# PIC_Schematic.net
KiCad netlist of a schematic drawn in Altium Designer
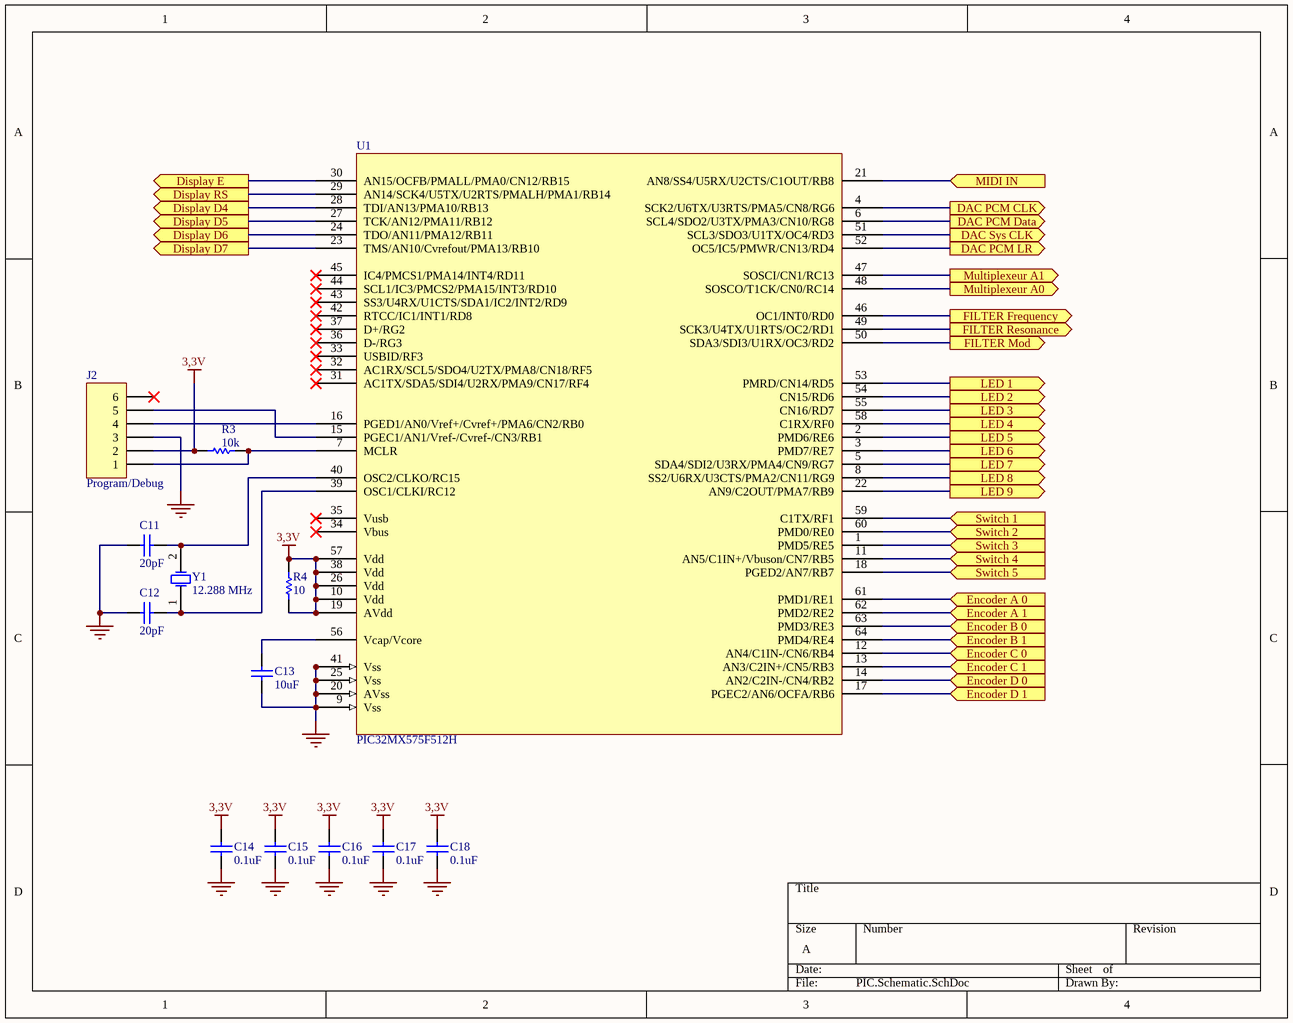
[diagram p0: PIC.Schematic.SchDoc]

(export (version "E")
  (design (tool "Eeschema 10.0.6"))
  (components
    (comp (ref "C11")
      (value "20pF")
      (footprint "CAPC1608N")
      (description "Capacitor (Semiconductor SIM Model)")
      (fields (field (name "PUBLISHER") "Altium Limited"))
      (libsource (lib "Miscellaneous Devices") (part "Cap Semi"))
    )
    (comp (ref "C12")
      (value "20pF")
      (footprint "CAPC1608N")
      (description "Capacitor (Semiconductor SIM Model)")
      (fields (field (name "PUBLISHER") "Altium Limited"))
      (libsource (lib "Miscellaneous Devices") (part "Cap Semi"))
    )
    (comp (ref "C13")
      (value "10uF")
      (footprint "CAPC1608N")
      (description "Capacitor")
      (fields (field (name "PUBLISHER") "Altium Limited"))
      (libsource (lib "Miscellaneous Devices") (part "Cap"))
    )
    (comp (ref "C14")
      (value "0.1uF")
      (footprint "CAPC1608N")
      (description "Capacitor (Semiconductor SIM Model)")
      (fields (field (name "PUBLISHER") "Altium Limited"))
      (libsource (lib "Miscellaneous Devices") (part "Cap Semi"))
    )
    (comp (ref "C15")
      (value "0.1uF")
      (footprint "CAPC1608N")
      (description "Capacitor (Semiconductor SIM Model)")
      (fields (field (name "PUBLISHER") "Altium Limited"))
      (libsource (lib "Miscellaneous Devices") (part "Cap Semi"))
    )
    (comp (ref "C16")
      (value "0.1uF")
      (footprint "CAPC1608N")
      (description "Capacitor (Semiconductor SIM Model)")
      (fields (field (name "PUBLISHER") "Altium Limited"))
      (libsource (lib "Miscellaneous Devices") (part "Cap Semi"))
    )
    (comp (ref "C17")
      (value "0.1uF")
      (footprint "CAPC1608N")
      (description "Capacitor (Semiconductor SIM Model)")
      (fields (field (name "PUBLISHER") "Altium Limited"))
      (libsource (lib "Miscellaneous Devices") (part "Cap Semi"))
    )
    (comp (ref "C18")
      (value "0.1uF")
      (footprint "CAPC1608N")
      (description "Capacitor (Semiconductor SIM Model)")
      (fields (field (name "PUBLISHER") "Altium Limited"))
      (libsource (lib "Miscellaneous Devices") (part "Cap Semi"))
    )
    (comp (ref "J2")
      (value "Program/Debug")
      (footprint "RJ11")
      (description "Header, 6-Pin, Right Angle")
      (fields (field (name "PUBLISHER") "Altium Limited"))
      (libsource (lib "Miscellaneous Connectors") (part "Header 6H"))
    )
    (comp (ref "R3")
      (value "10k")
      (footprint "CAPC1608N")
      (description "Resistor")
      (fields (field (name "PUBLISHER") "Altium Limited"))
      (libsource (lib "Miscellaneous Devices") (part "Res1"))
    )
    (comp (ref "R4")
      (value "10")
      (footprint "CAPC1608N")
      (description "Resistor")
      (fields (field (name "PUBLISHER") "Altium Limited"))
      (libsource (lib "Miscellaneous Devices") (part "Res1"))
    )
    (comp (ref "U1")
      (value "PIC32MX575F512H")
      (footprint "PIC32")
      (libsource (lib "SynthyTwo.Components") (part "PIC32 MX575F512H"))
    )
    (comp (ref "Y1")
      (value "12.288 MHz")
      (footprint "Xtal")
      (description "Crystal Oscillator")
      (fields (field (name "PUBLISHER") "Altium Limited"))
      (libsource (lib "Miscellaneous Devices") (part "XTAL"))
    )
  )
  (nets
    (net (code "1") (name "/DAC PCM CLK") (class "Default")
      (node (ref "U1") (pin "4") (pinfunction "SCK2/U6TX/U3RTS/PMA5/CN8/RG6_4") (pintype "passive"))
    )
    (net (code "2") (name "/DAC PCM Data") (class "Default")
      (node (ref "U1") (pin "6") (pinfunction "SCL4/SDO2/U3TX/PMA3/CN10/RG8_6") (pintype "passive"))
    )
    (net (code "3") (name "/DAC PCM LR") (class "Default")
      (node (ref "U1") (pin "52") (pinfunction "OC5/IC5/PMWR/CN13/RD4_52") (pintype "passive"))
    )
    (net (code "4") (name "/DAC Sys CLK") (class "Default")
      (node (ref "U1") (pin "51") (pinfunction "SCL3/SDO3/U1TX/OC4/RD3_51") (pintype "passive"))
    )
    (net (code "5") (name "/Display D4") (class "Default")
      (node (ref "U1") (pin "28") (pinfunction "TDI/AN13/PMA10/RB13_28") (pintype "passive"))
    )
    (net (code "6") (name "/Display D5") (class "Default")
      (node (ref "U1") (pin "27") (pinfunction "TCK/AN12/PMA11/RB12_27") (pintype "passive"))
    )
    (net (code "7") (name "/Display D6") (class "Default")
      (node (ref "U1") (pin "24") (pinfunction "TDO/AN11/PMA12/RB11_24") (pintype "passive"))
    )
    (net (code "8") (name "/Display D7") (class "Default")
      (node (ref "U1") (pin "23") (pinfunction "TMS/AN10/Cvrefout/PMA13/RB10_23") (pintype "passive"))
    )
    (net (code "9") (name "/Display E") (class "Default")
      (node (ref "U1") (pin "30") (pinfunction "AN15/OCFB/PMALL/PMA0/CN12/RB15_30") (pintype "passive"))
    )
    (net (code "10") (name "/Display RS") (class "Default")
      (node (ref "U1") (pin "29") (pinfunction "AN14/SCK4/U5TX/U2RTS/PMALH/PMA1/RB14_29") (pintype "passive"))
    )
    (net (code "11") (name "/Encoder A 0") (class "Default")
      (node (ref "U1") (pin "61") (pinfunction "PMD1/RE1_61") (pintype "passive"))
    )
    (net (code "12") (name "/Encoder A 1") (class "Default")
      (node (ref "U1") (pin "62") (pinfunction "PMD2/RE2_62") (pintype "passive"))
    )
    (net (code "13") (name "/Encoder B 0") (class "Default")
      (node (ref "U1") (pin "63") (pinfunction "PMD3/RE3_63") (pintype "passive"))
    )
    (net (code "14") (name "/Encoder B 1") (class "Default")
      (node (ref "U1") (pin "64") (pinfunction "PMD4/RE4_64") (pintype "passive"))
    )
    (net (code "15") (name "/Encoder C 0") (class "Default")
      (node (ref "U1") (pin "12") (pinfunction "AN4/C1IN-/CN6/RB4_12") (pintype "passive"))
    )
    (net (code "16") (name "/Encoder C 1") (class "Default")
      (node (ref "U1") (pin "13") (pinfunction "AN3/C2IN+/CN5/RB3_13") (pintype "passive"))
    )
    (net (code "17") (name "/Encoder D 0") (class "Default")
      (node (ref "U1") (pin "14") (pinfunction "AN2/C2IN-/CN4/RB2_14") (pintype "passive"))
    )
    (net (code "18") (name "/Encoder D 1") (class "Default")
      (node (ref "U1") (pin "17") (pinfunction "PGEC2/AN6/OCFA/RB6_17") (pintype "passive"))
    )
    (net (code "19") (name "/FILTER Frequency") (class "Default")
      (node (ref "U1") (pin "46") (pinfunction "OC1/INT0/RD0_46") (pintype "passive"))
    )
    (net (code "20") (name "/FILTER Mod") (class "Default")
      (node (ref "U1") (pin "50") (pinfunction "SDA3/SDI3/U1RX/OC3/RD2_50") (pintype "passive"))
    )
    (net (code "21") (name "/FILTER Resonance") (class "Default")
      (node (ref "U1") (pin "49") (pinfunction "SCK3/U4TX/U1RTS/OC2/RD1_49") (pintype "passive"))
    )
    (net (code "22") (name "/LED 1") (class "Default")
      (node (ref "U1") (pin "53") (pinfunction "PMRD/CN14/RD5_53") (pintype "passive"))
    )
    (net (code "23") (name "/LED 2") (class "Default")
      (node (ref "U1") (pin "54") (pinfunction "CN15/RD6_54") (pintype "passive"))
    )
    (net (code "24") (name "/LED 3") (class "Default")
      (node (ref "U1") (pin "55") (pinfunction "CN16/RD7_55") (pintype "passive"))
    )
    (net (code "25") (name "/LED 4") (class "Default")
      (node (ref "U1") (pin "58") (pinfunction "C1RX/RF0_58") (pintype "passive"))
    )
    (net (code "26") (name "/LED 5") (class "Default")
      (node (ref "U1") (pin "2") (pinfunction "PMD6/RE6_2") (pintype "passive"))
    )
    (net (code "27") (name "/LED 6") (class "Default")
      (node (ref "U1") (pin "3") (pinfunction "PMD7/RE7_3") (pintype "passive"))
    )
    (net (code "28") (name "/LED 7") (class "Default")
      (node (ref "U1") (pin "5") (pinfunction "SDA4/SDI2/U3RX/PMA4/CN9/RG7_5") (pintype "passive"))
    )
    (net (code "29") (name "/LED 8") (class "Default")
      (node (ref "U1") (pin "8") (pinfunction "SS2/U6RX/U3CTS/PMA2/CN11/RG9_8") (pintype "passive"))
    )
    (net (code "30") (name "/LED 9") (class "Default")
      (node (ref "U1") (pin "22") (pinfunction "AN9/C2OUT/PMA7/RB9_22") (pintype "passive"))
    )
    (net (code "31") (name "/MIDI IN") (class "Default")
      (node (ref "U1") (pin "21") (pinfunction "AN8/SS4/U5RX/U2CTS/C1OUT/RB8_21") (pintype "passive"))
    )
    (net (code "32") (name "/Multiplexeur A0") (class "Default")
      (node (ref "U1") (pin "48") (pinfunction "SOSCO/T1CK/CN0/RC14_48") (pintype "passive"))
    )
    (net (code "33") (name "/Multiplexeur A1") (class "Default")
      (node (ref "U1") (pin "47") (pinfunction "SOSCI/CN1/RC13_47") (pintype "passive"))
    )
    (net (code "34") (name "/Switch 1") (class "Default")
      (node (ref "U1") (pin "59") (pinfunction "C1TX/RF1_59") (pintype "passive"))
    )
    (net (code "35") (name "/Switch 2") (class "Default")
      (node (ref "U1") (pin "60") (pinfunction "PMD0/RE0_60") (pintype "passive"))
    )
    (net (code "36") (name "/Switch 3") (class "Default")
      (node (ref "U1") (pin "1") (pinfunction "PMD5/RE5_1") (pintype "passive"))
    )
    (net (code "37") (name "/Switch 4") (class "Default")
      (node (ref "U1") (pin "11") (pinfunction "AN5/C1IN+/Vbuson/CN7/RB5_11") (pintype "passive"))
    )
    (net (code "38") (name "/Switch 5") (class "Default")
      (node (ref "U1") (pin "18") (pinfunction "PGED2/AN7/RB7_18") (pintype "passive"))
    )
    (net (code "39") (name "3,3V") (class "Default")
      (node (ref "C14") (pin "2") (pinfunction "2_2") (pintype "passive"))
      (node (ref "C15") (pin "2") (pinfunction "2_2") (pintype "passive"))
      (node (ref "C16") (pin "2") (pinfunction "2_2") (pintype "passive"))
      (node (ref "C17") (pin "2") (pinfunction "2_2") (pintype "passive"))
      (node (ref "C18") (pin "2") (pinfunction "2_2") (pintype "passive"))
      (node (ref "J2") (pin "2") (pinfunction "2_2") (pintype "passive"))
      (node (ref "R3") (pin "2") (pinfunction "2_2") (pintype "passive"))
      (node (ref "R4") (pin "1") (pinfunction "1_1") (pintype "passive"))
      (node (ref "R4") (pin "2") (pinfunction "2_2") (pintype "passive"))
      (node (ref "U1") (pin "10") (pinfunction "Vdd_10") (pintype "passive"))
      (node (ref "U1") (pin "19") (pinfunction "AVdd_19") (pintype "passive"))
      (node (ref "U1") (pin "26") (pinfunction "Vdd_26") (pintype "passive"))
      (node (ref "U1") (pin "38") (pinfunction "Vdd_38") (pintype "passive"))
      (node (ref "U1") (pin "57") (pinfunction "Vdd_57") (pintype "passive"))
    )
    (net (code "40") (name "GND") (class "Default")
      (node (ref "C11") (pin "1") (pinfunction "1_1") (pintype "passive"))
      (node (ref "C12") (pin "1") (pinfunction "1_1") (pintype "passive"))
      (node (ref "C13") (pin "1") (pinfunction "1_1") (pintype "passive"))
      (node (ref "C14") (pin "1") (pinfunction "1_1") (pintype "passive"))
      (node (ref "C15") (pin "1") (pinfunction "1_1") (pintype "passive"))
      (node (ref "C16") (pin "1") (pinfunction "1_1") (pintype "passive"))
      (node (ref "C17") (pin "1") (pinfunction "1_1") (pintype "passive"))
      (node (ref "C18") (pin "1") (pinfunction "1_1") (pintype "passive"))
      (node (ref "J2") (pin "3") (pinfunction "3_3") (pintype "passive"))
      (node (ref "U1") (pin "20") (pinfunction "AVss_20") (pintype "input"))
      (node (ref "U1") (pin "25") (pinfunction "Vss_25") (pintype "input"))
      (node (ref "U1") (pin "41") (pinfunction "Vss_41") (pintype "input"))
      (node (ref "U1") (pin "9") (pinfunction "Vss_9") (pintype "input"))
    )
    (net (code "41") (name "Net-(U1-MCLR)") (class "Default")
      (node (ref "J2") (pin "1") (pinfunction "1_1") (pintype "passive"))
      (node (ref "R3") (pin "1") (pinfunction "1_1") (pintype "passive"))
      (node (ref "U1") (pin "7") (pinfunction "MCLR_7") (pintype "passive"))
    )
    (net (code "42") (name "Net-(U1-OSC1{slash}CLKI{slash}RC12)") (class "Default")
      (node (ref "C12") (pin "2") (pinfunction "2_2") (pintype "passive"))
      (node (ref "U1") (pin "39") (pinfunction "OSC1/CLKI/RC12_39") (pintype "passive"))
      (node (ref "Y1") (pin "1") (pinfunction "OSC1_1") (pintype "passive"))
    )
    (net (code "43") (name "Net-(U1-OSC2{slash}CLKO{slash}RC15)") (class "Default")
      (node (ref "C11") (pin "2") (pinfunction "2_2") (pintype "passive"))
      (node (ref "U1") (pin "40") (pinfunction "OSC2/CLKO/RC15_40") (pintype "passive"))
      (node (ref "Y1") (pin "2") (pinfunction "OSC2_2") (pintype "passive"))
    )
    (net (code "44") (name "Net-(U1-PGEC1{slash}AN1{slash}Vref-{slash}Cvref-{slash}CN3{slash}RB1)") (class "Default")
      (node (ref "J2") (pin "5") (pinfunction "5_5") (pintype "passive"))
      (node (ref "U1") (pin "15") (pinfunction "PGEC1/AN1/Vref-/Cvref-/CN3/RB1_15") (pintype "passive"))
    )
    (net (code "45") (name "Net-(U1-PGED1{slash}AN0{slash}Vref+{slash}Cvref+{slash}PMA6{slash}CN2{slash}RB0)") (class "Default")
      (node (ref "J2") (pin "4") (pinfunction "4_4") (pintype "passive"))
      (node (ref "U1") (pin "16") (pinfunction "PGED1/AN0/Vref+/Cvref+/PMA6/CN2/RB0_16") (pintype "passive"))
    )
    (net (code "46") (name "Net-(U1-Vcap{slash}Vcore)") (class "Default")
      (node (ref "C13") (pin "2") (pinfunction "2_2") (pintype "passive"))
      (node (ref "U1") (pin "56") (pinfunction "Vcap/Vcore_56") (pintype "passive"))
    )
    (net (code "47") (name "unconnected-(J2-Pad6)") (class "Default")
      (node (ref "J2") (pin "6") (pinfunction "6_6") (pintype "passive+no_connect"))
    )
    (net (code "48") (name "unconnected-(U1-AC1RX{slash}SCL5{slash}SDO4{slash}U2TX{slash}PMA8{slash}CN18{slash}RF5-Pad32)") (class "Default")
      (node (ref "U1") (pin "32") (pinfunction "AC1RX/SCL5/SDO4/U2TX/PMA8/CN18/RF5_32") (pintype "passive+no_connect"))
    )
    (net (code "49") (name "unconnected-(U1-AC1TX{slash}SDA5{slash}SDI4{slash}U2RX{slash}PMA9{slash}CN17{slash}RF4-Pad31)") (class "Default")
      (node (ref "U1") (pin "31") (pinfunction "AC1TX/SDA5/SDI4/U2RX/PMA9/CN17/RF4_31") (pintype "passive+no_connect"))
    )
    (net (code "50") (name "unconnected-(U1-D+{slash}RG2-Pad37)") (class "Default")
      (node (ref "U1") (pin "37") (pinfunction "D+/RG2_37") (pintype "passive+no_connect"))
    )
    (net (code "51") (name "unconnected-(U1-D-{slash}RG3-Pad36)") (class "Default")
      (node (ref "U1") (pin "36") (pinfunction "D-/RG3_36") (pintype "passive+no_connect"))
    )
    (net (code "52") (name "unconnected-(U1-IC4{slash}PMCS1{slash}PMA14{slash}INT4{slash}RD11-Pad45)") (class "Default")
      (node (ref "U1") (pin "45") (pinfunction "IC4/PMCS1/PMA14/INT4/RD11_45") (pintype "passive+no_connect"))
    )
    (net (code "53") (name "unconnected-(U1-RTCC{slash}IC1{slash}INT1{slash}RD8-Pad42)") (class "Default")
      (node (ref "U1") (pin "42") (pinfunction "RTCC/IC1/INT1/RD8_42") (pintype "passive+no_connect"))
    )
    (net (code "54") (name "unconnected-(U1-SCL1{slash}IC3{slash}PMCS2{slash}PMA15{slash}INT3{slash}RD10-Pad44)") (class "Default")
      (node (ref "U1") (pin "44") (pinfunction "SCL1/IC3/PMCS2/PMA15/INT3/RD10_44") (pintype "passive+no_connect"))
    )
    (net (code "55") (name "unconnected-(U1-SS3{slash}U4RX{slash}U1CTS{slash}SDA1{slash}IC2{slash}INT2{slash}RD9-Pad43)") (class "Default")
      (node (ref "U1") (pin "43") (pinfunction "SS3/U4RX/U1CTS/SDA1/IC2/INT2/RD9_43") (pintype "passive+no_connect"))
    )
    (net (code "56") (name "unconnected-(U1-USBID{slash}RF3-Pad33)") (class "Default")
      (node (ref "U1") (pin "33") (pinfunction "USBID/RF3_33") (pintype "passive+no_connect"))
    )
    (net (code "57") (name "unconnected-(U1-Vbus-Pad34)") (class "Default")
      (node (ref "U1") (pin "34") (pinfunction "Vbus_34") (pintype "passive+no_connect"))
    )
    (net (code "58") (name "unconnected-(U1-Vusb-Pad35)") (class "Default")
      (node (ref "U1") (pin "35") (pinfunction "Vusb_35") (pintype "passive+no_connect"))
    )
  )
)
